# RightInterface.net
KiCad netlist of a schematic drawn in Altium Designer
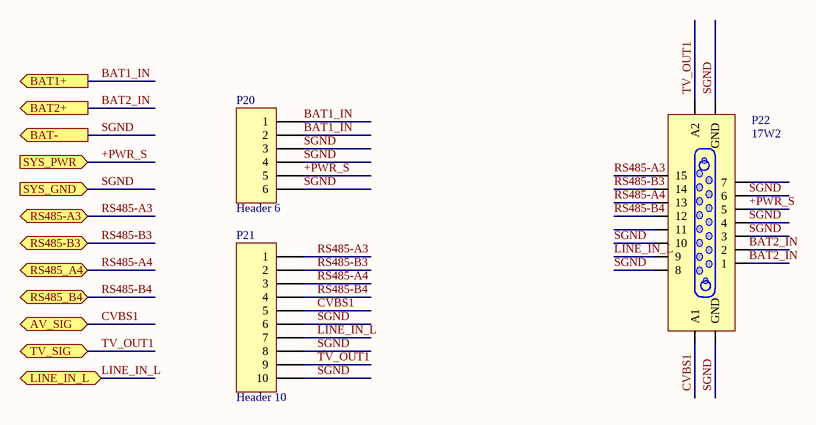
[diagram p0: RightInterface.SchDoc]

(export (version "E")
  (design (tool "Eeschema 10.0.6"))
  (components
    (comp (ref "P20")
      (value "Header 6")
      (footprint "DS1X6-2.54")
      (description "Header, 6-Pin")
      (fields (field (name "PUBLISHER") "Altium Limited"))
      (libsource (lib "Miscellaneous Connectors") (part "Header 6"))
    )
    (comp (ref "P21")
      (value "Header 10")
      (footprint "DS1X10-2.54")
      (description "Header, 10-Pin")
      (fields (field (name "PUBLISHER") "Altium Limited"))
      (libsource (lib "Miscellaneous Connectors") (part "Header 10"))
    )
    (comp (ref "P22")
      (value "17W2")
      (footprint "17W2_FEMALE")
      (description "Connector")
      (libsource (lib "Connector Class") (part "17W2"))
    )
  )
  (nets
    (net (code "1") (name "/+PWR_S") (class "Default")
      (node (ref "P20") (pin "5") (pinfunction "5_5") (pintype "passive"))
      (node (ref "P22") (pin "5") (pinfunction "5_5") (pintype "passive"))
    )
    (net (code "2") (name "/BAT1_IN") (class "Default")
      (node (ref "P20") (pin "1") (pinfunction "1_1") (pintype "passive"))
      (node (ref "P20") (pin "2") (pinfunction "2_2") (pintype "passive"))
    )
    (net (code "3") (name "/BAT2_IN") (class "Default")
      (node (ref "P22") (pin "1") (pinfunction "1_1") (pintype "passive"))
      (node (ref "P22") (pin "2") (pinfunction "2_2") (pintype "passive"))
    )
    (net (code "4") (name "/CVBS1") (class "Default")
      (node (ref "P21") (pin "5") (pinfunction "5_5") (pintype "passive"))
      (node (ref "P22") (pin "16") (pinfunction "A1_16") (pintype "passive"))
    )
    (net (code "5") (name "/LINE_IN_L") (class "Default")
      (node (ref "P21") (pin "7") (pinfunction "7_7") (pintype "passive"))
      (node (ref "P22") (pin "9") (pinfunction "9_9") (pintype "passive"))
    )
    (net (code "6") (name "/RS485-A3") (class "Default")
      (node (ref "P21") (pin "1") (pinfunction "1_1") (pintype "passive"))
      (node (ref "P22") (pin "15") (pinfunction "15_15") (pintype "passive"))
    )
    (net (code "7") (name "/RS485-A4") (class "Default")
      (node (ref "P21") (pin "3") (pinfunction "3_3") (pintype "passive"))
      (node (ref "P22") (pin "13") (pinfunction "13_13") (pintype "passive"))
    )
    (net (code "8") (name "/RS485-B3") (class "Default")
      (node (ref "P21") (pin "2") (pinfunction "2_2") (pintype "passive"))
      (node (ref "P22") (pin "14") (pinfunction "14_14") (pintype "passive"))
    )
    (net (code "9") (name "/RS485-B4") (class "Default")
      (node (ref "P21") (pin "4") (pinfunction "4_4") (pintype "passive"))
      (node (ref "P22") (pin "12") (pinfunction "12_12") (pintype "passive"))
    )
    (net (code "10") (name "/SGND") (class "Default")
      (node (ref "P20") (pin "3") (pinfunction "3_3") (pintype "passive"))
      (node (ref "P20") (pin "4") (pinfunction "4_4") (pintype "passive"))
      (node (ref "P20") (pin "6") (pinfunction "6_6") (pintype "passive"))
      (node (ref "P21") (pin "10") (pinfunction "10_10") (pintype "passive"))
      (node (ref "P21") (pin "6") (pinfunction "6_6") (pintype "passive"))
      (node (ref "P21") (pin "8") (pinfunction "8_8") (pintype "passive"))
      (node (ref "P22") (pin "10") (pinfunction "10_10") (pintype "passive"))
      (node (ref "P22") (pin "17") (pinfunction "GND_17") (pintype "passive"))
      (node (ref "P22") (pin "19") (pinfunction "GND_19") (pintype "passive"))
      (node (ref "P22") (pin "3") (pinfunction "3_3") (pintype "passive"))
      (node (ref "P22") (pin "4") (pinfunction "4_4") (pintype "passive"))
      (node (ref "P22") (pin "6") (pinfunction "6_6") (pintype "passive"))
      (node (ref "P22") (pin "8") (pinfunction "8_8") (pintype "passive"))
    )
    (net (code "11") (name "/TV_OUT1") (class "Default")
      (node (ref "P21") (pin "9") (pinfunction "9_9") (pintype "passive"))
      (node (ref "P22") (pin "18") (pinfunction "A2_18") (pintype "passive"))
    )
    (net (code "12") (name "unconnected-(P22-Pad7)") (class "Default")
      (node (ref "P22") (pin "7") (pinfunction "7_7") (pintype "passive"))
    )
    (net (code "13") (name "unconnected-(P22-Pad11)") (class "Default")
      (node (ref "P22") (pin "11") (pinfunction "11_11") (pintype "passive"))
    )
  )
)
